# RS232_NPN_PNP_FTDI.net
KiCad netlist of a schematic drawn in EAGLE
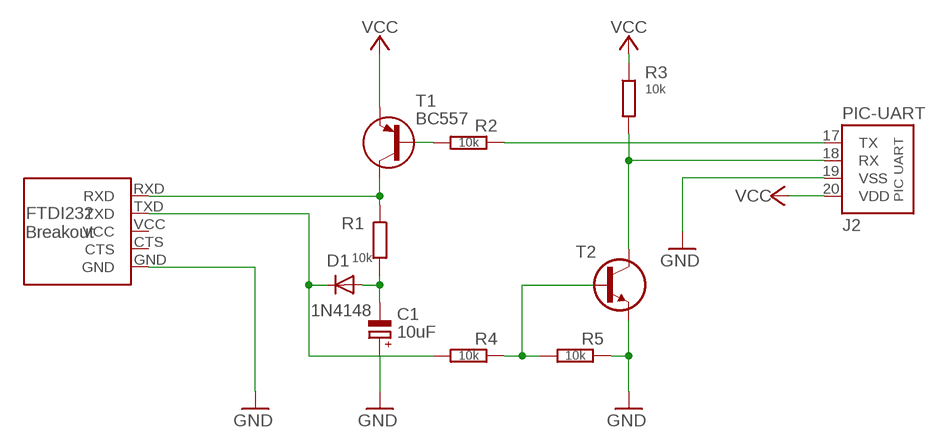
[diagram p0: schematic, sheet 1]

(export (version "E")
  (design (tool "Eeschema 10.0.6"))
  (components
    (comp (ref "C1")
      (value "10uF")
      (footprint "eagle-import:E5-4")
      (libsource (lib "eagle-import") (part "CPOLE5-4"))
    )
    (comp (ref "D1")
      (value "1N4148")
      (footprint "eagle-import:DO34-5V")
      (libsource (lib "eagle-import") (part "1N414834-5V"))
    )
    (comp (ref "J1")
      (value "FTDI232-BO-5P-L")
      (footprint "eagle-import:FTDI232-BO-5-L")
      (libsource (lib "eagle-import") (part "FTDI232-BO-5P-L"))
    )
    (comp (ref "J2")
      (value "PIC-UART")
      (footprint "eagle-import:PIC-UART")
      (libsource (lib "eagle-import") (part "PIC-UART"))
    )
    (comp (ref "R1")
      (value "10k")
      (footprint "eagle-import:0202_5-V")
      (libsource (lib "eagle-import") (part "R0202/5-V"))
    )
    (comp (ref "R2")
      (value "10k")
      (footprint "eagle-import:0202_7")
      (libsource (lib "eagle-import") (part "R0202/7"))
    )
    (comp (ref "R3")
      (value "10k")
      (footprint "eagle-import:0202_7")
      (libsource (lib "eagle-import") (part "R0202/7"))
    )
    (comp (ref "R4")
      (value "10k")
      (footprint "eagle-import:0202_7-V")
      (libsource (lib "eagle-import") (part "R0202/7-V"))
    )
    (comp (ref "R5")
      (value "10k")
      (footprint "eagle-import:0202_7")
      (libsource (lib "eagle-import") (part "R0202/7"))
    )
    (comp (ref "T1")
      (value "BC557")
      (footprint "eagle-import:TO92-CBE")
      (libsource (lib "eagle-import") (part "BC557CBE"))
    )
    (comp (ref "T2")
      (value "BC547")
      (footprint "eagle-import:TO92-CBE")
      (libsource (lib "eagle-import") (part "BC547CBE"))
    )
  )
  (nets
    (net (code "1") (name "GND") (class "Default")
      (node (ref "C1") (pin "+") (pinfunction "+_+") (pintype "passive"))
      (node (ref "J1") (pin "GND") (pinfunction "GND_GND") (pintype "bidirectional"))
      (node (ref "J2") (pin "19") (pinfunction "VSS_19") (pintype "passive"))
      (node (ref "R5") (pin "1") (pinfunction "1_1") (pintype "passive"))
      (node (ref "T2") (pin "E") (pinfunction "E_E") (pintype "passive"))
    )
    (net (code "2") (name "Net-(C1-Pad-)") (class "Default")
      (node (ref "C1") (pin "-") (pinfunction "-_-") (pintype "passive"))
      (node (ref "D1") (pin "A") (pinfunction "A_A") (pintype "passive"))
      (node (ref "R1") (pin "2") (pinfunction "2_2") (pintype "passive"))
    )
    (net (code "3") (name "Net-(D1-PadC)") (class "Default")
      (node (ref "D1") (pin "C") (pinfunction "C_C") (pintype "passive"))
      (node (ref "J1") (pin "TXD") (pinfunction "TXD_TXD") (pintype "bidirectional"))
      (node (ref "R4") (pin "2") (pinfunction "2_2") (pintype "passive"))
    )
    (net (code "4") (name "Net-(J1-PadRXD)") (class "Default")
      (node (ref "J1") (pin "RXD") (pinfunction "RXD_RXD") (pintype "bidirectional"))
      (node (ref "R1") (pin "1") (pinfunction "1_1") (pintype "passive"))
      (node (ref "T1") (pin "C") (pinfunction "C_C") (pintype "passive"))
    )
    (net (code "5") (name "Net-(J2-RX)") (class "Default")
      (node (ref "J2") (pin "18") (pinfunction "RX_18") (pintype "passive"))
      (node (ref "R3") (pin "2") (pinfunction "2_2") (pintype "passive"))
      (node (ref "T2") (pin "C") (pinfunction "C_C") (pintype "passive"))
    )
    (net (code "6") (name "Net-(J2-TX)") (class "Default")
      (node (ref "J2") (pin "17") (pinfunction "TX_17") (pintype "passive"))
      (node (ref "R2") (pin "1") (pinfunction "1_1") (pintype "passive"))
    )
    (net (code "7") (name "Net-(R2-Pad2)") (class "Default")
      (node (ref "R2") (pin "2") (pinfunction "2_2") (pintype "passive"))
      (node (ref "T1") (pin "B") (pinfunction "B_B") (pintype "passive"))
    )
    (net (code "8") (name "Net-(R4-Pad1)") (class "Default")
      (node (ref "R4") (pin "1") (pinfunction "1_1") (pintype "passive"))
      (node (ref "R5") (pin "2") (pinfunction "2_2") (pintype "passive"))
      (node (ref "T2") (pin "B") (pinfunction "B_B") (pintype "passive"))
    )
    (net (code "9") (name "VCC") (class "Default")
      (node (ref "J2") (pin "20") (pinfunction "VDD_20") (pintype "passive"))
      (node (ref "R3") (pin "1") (pinfunction "1_1") (pintype "passive"))
      (node (ref "T1") (pin "E") (pinfunction "E_E") (pintype "passive"))
    )
    (net (code "10") (name "unconnected-(J1-PadCTS)") (class "Default")
      (node (ref "J1") (pin "CTS") (pinfunction "CTS_CTS") (pintype "bidirectional"))
    )
    (net (code "11") (name "unconnected-(J1-PadVCC)") (class "Default")
      (node (ref "J1") (pin "VCC") (pinfunction "VCC_VCC") (pintype "bidirectional"))
    )
  )
)
